# bluetooth.net
KiCad netlist of a schematic drawn in EAGLE
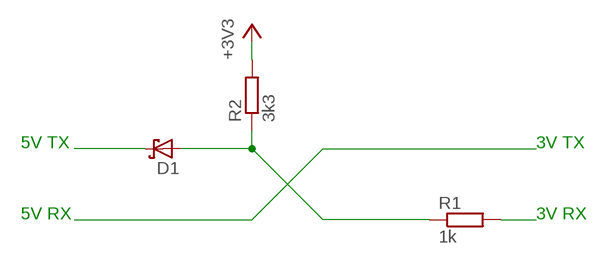
[diagram p0: schematic, sheet 1]

(export (version "E")
  (design (tool "Eeschema 10.0.6"))
  (components
    (comp (ref "D1")
      (value "SCHOTTKY-DIODEF126Z12")
      (footprint "eagle-import:F126Z12")
      (libsource (lib "eagle-import") (part "SCHOTTKY-DIODEF126Z12"))
    )
    (comp (ref "R1")
      (value "1k")
      (footprint "eagle-import:0207_5V")
      (libsource (lib "eagle-import") (part "R-EU_0207/5V"))
    )
    (comp (ref "R2")
      (value "3k3")
      (footprint "eagle-import:0207_5V")
      (libsource (lib "eagle-import") (part "R-EU_0207/5V"))
    )
  )
  (nets
    (net (code "1") (name "+3V3") (class "Default")
      (node (ref "R2") (pin "2") (pinfunction "2_2") (pintype "passive"))
    )
    (net (code "2") (name "Net-(D1-PadA)") (class "Default")
      (node (ref "D1") (pin "A") (pinfunction "A_A") (pintype "passive"))
      (node (ref "R1") (pin "1") (pinfunction "1_1") (pintype "passive"))
      (node (ref "R2") (pin "1") (pinfunction "1_1") (pintype "passive"))
    )
    (net (code "3") (name "unconnected-(D1-PadC)") (class "Default")
      (node (ref "D1") (pin "C") (pinfunction "C_C") (pintype "passive"))
    )
    (net (code "4") (name "unconnected-(R1-Pad2)") (class "Default")
      (node (ref "R1") (pin "2") (pinfunction "2_2") (pintype "passive"))
    )
  )
)
